# cs301_Group2_Offsets.net
KiCad netlist of a schematic drawn in Altium Designer
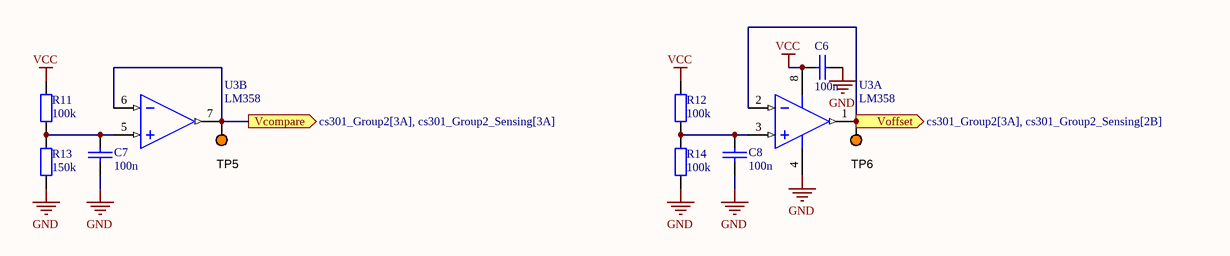
[diagram p0: cs301_Group2_Offsets.SchDoc]

(export (version "E")
  (design (tool "Eeschema 10.0.6"))
  (components
    (comp (ref "C6")
      (value "100n")
      (footprint "0805 CAP")
      (description "SMT ceramic capacitor 0805 size")
      (libsource (lib "EE209_Library") (part "CerCap_SMT_0805"))
    )
    (comp (ref "C7")
      (value "100n")
      (footprint "0805 CAP")
      (description "SMT ceramic capacitor 0805 size")
      (libsource (lib "EE209_Library") (part "CerCap_SMT_0805"))
    )
    (comp (ref "C8")
      (value "100n")
      (footprint "0805 CAP")
      (description "SMT ceramic capacitor 0805 size")
      (libsource (lib "EE209_Library") (part "CerCap_SMT_0805"))
    )
    (comp (ref "R11")
      (value "100k")
      (footprint "0805 RES")
      (description "0805 resistor")
      (fields (field (name "PUBLISHER") "Altium Limited"))
      (libsource (lib "EE209_Library") (part "Res_SMT_0805"))
    )
    (comp (ref "R12")
      (value "100k")
      (footprint "0805 RES")
      (description "0805 resistor")
      (fields (field (name "PUBLISHER") "Altium Limited"))
      (libsource (lib "EE209_Library") (part "Res_SMT_0805"))
    )
    (comp (ref "R13")
      (value "150k")
      (footprint "0805 RES")
      (description "0805 resistor")
      (fields (field (name "PUBLISHER") "Altium Limited"))
      (libsource (lib "EE209_Library") (part "Res_SMT_0805"))
    )
    (comp (ref "R14")
      (value "100k")
      (footprint "0805 RES")
      (description "0805 resistor")
      (fields (field (name "PUBLISHER") "Altium Limited"))
      (libsource (lib "EE209_Library") (part "Res_SMT_0805"))
    )
    (comp (ref "TP5")
      (value "5003")
      (footprint "TP_TH")
      (description "Test Point, Orange, 1-Pin THD, RoHS")
      (libsource (lib "EE209_Library") (part "TestPoint"))
    )
    (comp (ref "TP6")
      (value "5003")
      (footprint "TP_TH")
      (description "Test Point, Orange, 1-Pin THD, RoHS")
      (libsource (lib "EE209_Library") (part "TestPoint"))
    )
    (comp (ref "U3")
      (value "LM358")
      (footprint "SO - 8")
      (description "IC OPAMP 8SOIC")
      (libsource (lib "EE209_Library") (part "LM358_SMT_SOIC8"))
    )
  )
  (nets
    (net (code "1") (name "/Vcompare") (class "Default")
      (node (ref "TP5") (pin "1") (pinfunction "1_1") (pintype "passive"))
      (node (ref "U3") (pin "6") (pinfunction "VINA-_6") (pintype "input"))
      (node (ref "U3") (pin "7") (pinfunction "VOUTA_7") (pintype "output"))
    )
    (net (code "2") (name "/Voffset") (class "Default")
      (node (ref "TP6") (pin "1") (pinfunction "1_1") (pintype "passive"))
      (node (ref "U3") (pin "1") (pinfunction "VOUTA_1") (pintype "output"))
      (node (ref "U3") (pin "2") (pinfunction "VINA-_2") (pintype "input"))
    )
    (net (code "3") (name "GND") (class "Default")
      (node (ref "C6") (pin "2") (pinfunction "2_2") (pintype "passive"))
      (node (ref "C7") (pin "1") (pinfunction "1_1") (pintype "passive"))
      (node (ref "C8") (pin "1") (pinfunction "1_1") (pintype "passive"))
      (node (ref "R13") (pin "2") (pinfunction "2_2") (pintype "passive"))
      (node (ref "R14") (pin "2") (pinfunction "2_2") (pintype "passive"))
      (node (ref "U3") (pin "4") (pinfunction "VSS_4") (pintype "power_in"))
    )
    (net (code "4") (name "Net-(U3A-VINA+)") (class "Default")
      (node (ref "C8") (pin "2") (pinfunction "2_2") (pintype "passive"))
      (node (ref "R12") (pin "2") (pinfunction "2_2") (pintype "passive"))
      (node (ref "R14") (pin "1") (pinfunction "1_1") (pintype "passive"))
      (node (ref "U3") (pin "3") (pinfunction "VINA+_3") (pintype "input"))
    )
    (net (code "5") (name "Net-(U3B-VINA+)") (class "Default")
      (node (ref "C7") (pin "2") (pinfunction "2_2") (pintype "passive"))
      (node (ref "R11") (pin "2") (pinfunction "2_2") (pintype "passive"))
      (node (ref "R13") (pin "1") (pinfunction "1_1") (pintype "passive"))
      (node (ref "U3") (pin "5") (pinfunction "VINA+_5") (pintype "input"))
    )
    (net (code "6") (name "VCC") (class "Default")
      (node (ref "C6") (pin "1") (pinfunction "1_1") (pintype "passive"))
      (node (ref "R11") (pin "1") (pinfunction "1_1") (pintype "passive"))
      (node (ref "R12") (pin "1") (pinfunction "1_1") (pintype "passive"))
      (node (ref "U3") (pin "8") (pinfunction "VDD_8") (pintype "power_in"))
    )
  )
)
